# 12V_Power_Supply.net
KiCad netlist of a schematic drawn in Altium Designer
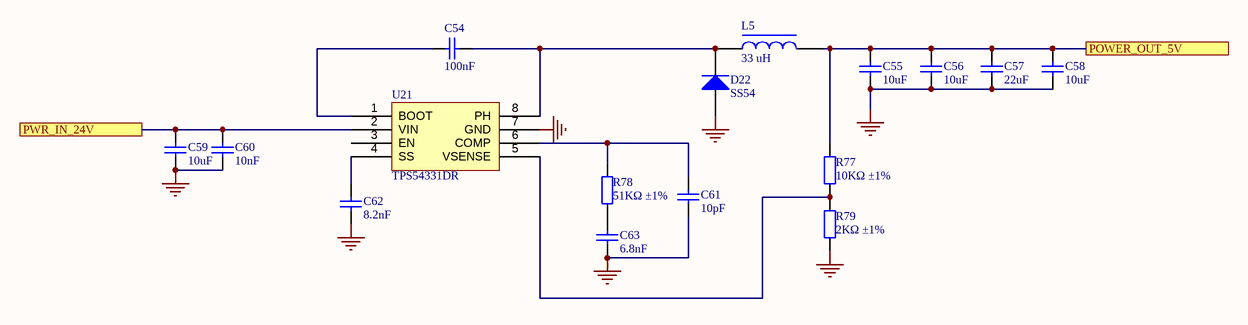
[diagram p0: 12V_Power_Supply.SchDoc]

(export (version "E")
  (design (tool "Eeschema 10.0.6"))
  (components
    (comp (ref "C54")
      (value "100nF")
      (footprint "0603_C")
      (description "Chip capacitors")
      (fields (field (name "MANUFACTURER") "YAGEO") (field (name "PARTNUMBER") "CC0603KRX7R9BB104"))
      (libsource (lib "Cap") (part "0603 100nF (104) 10% 50V"))
    )
    (comp (ref "C55")
      (value "10uF")
      (footprint "0603_C")
      (description "Chip capacitors")
      (fields
        (field (name "MANUFACTURER") "Samsung Electro-Mechanics")
        (field (name "PARTNUMBER") "CL10A106KP8NNNC")
      )
      (libsource (lib "Cap") (part "0603 10uF (106) 10% 10V"))
    )
    (comp (ref "C56")
      (value "10uF")
      (footprint "0603_C")
      (description "Chip capacitors")
      (fields
        (field (name "MANUFACTURER") "Samsung Electro-Mechanics")
        (field (name "PARTNUMBER") "CL10A106KP8NNNC")
      )
      (libsource (lib "Cap") (part "0603 10uF (106) 10% 10V"))
    )
    (comp (ref "C57")
      (value "22uF")
      (footprint "0805_C")
      (description "Chip capacitors")
      (fields
        (field (name "MANUFACTURER") "Samsung Electro-Mechanics")
        (field (name "PARTNUMBER") "CL21A226MAQNNNE")
      )
      (libsource (lib "Cap") (part "0805 22uF (226) 20% 25V"))
    )
    (comp (ref "C58")
      (value "10uF")
      (footprint "0603_C")
      (description "Chip capacitors")
      (fields
        (field (name "MANUFACTURER") "Samsung Electro-Mechanics")
        (field (name "PARTNUMBER") "CL10A106KP8NNNC")
      )
      (libsource (lib "Cap") (part "0603 10uF (106) 10% 10V"))
    )
    (comp (ref "C59")
      (value "10uF")
      (footprint "1206_C")
      (description "Chip capacitors")
      (fields
        (field (name "MANUFACTURER") "Samsung Electro-Mechanics")
        (field (name "PARTNUMBER") "CL31A106KBHNNNE")
      )
      (libsource (lib "Cap") (part "1206 10uF (106) 10% 50V"))
    )
    (comp (ref "C60")
      (value "10nF")
      (footprint "0402_C")
      (description "Chip capacitors")
      (fields
        (field (name "MANUFACTURER") "Samsung Electro-Mechanics")
        (field (name "PARTNUMBER") "CL05B103KB5NNNC")
      )
      (libsource (lib "Cap") (part "0402 10nF (103) 10% 50V"))
    )
    (comp (ref "C61")
      (value "10pF")
      (footprint "0402_C")
      (description "Chip capacitors")
      (fields
        (field (name "MANUFACTURER") "Samsung Electro-Mechanics")
        (field (name "PARTNUMBER") "CL05C100JB5NNNC")
      )
      (libsource (lib "Cap") (part "0402 10pF (100) 5% 50V"))
    )
    (comp (ref "C62")
      (value "8.2nF")
      (footprint "0603_C")
      (description "Chip capacitors")
      (fields
        (field (name "MANUFACTURER") "Samsung Electro-Mechanics")
        (field (name "PARTNUMBER") "CL10B822KB8NNNC")
      )
      (libsource (lib "Cap") (part "0603 8.2nF (822) 10% 50V"))
    )
    (comp (ref "C63")
      (value "6.8nF")
      (footprint "0402_C")
      (description "Chip capacitors")
      (fields
        (field (name "MANUFACTURER") "Guangdong Fenghua Advanced Tech")
        (field (name "PARTNUMBER") "0402B682K500NT")
      )
      (libsource (lib "Cap") (part "0402 6.8nF (682) 10% 50V"))
    )
    (comp (ref "D22")
      (value "SS54")
      (footprint "SMA(DO-214AC)_S1")
      (description "二极管")
      (libsource (lib "Diode") (part "SMA(DO-214AC) SS54"))
    )
    (comp (ref "L5")
      (value "33 uH")
      (footprint "INDPM7366X300N")
      (description "33uH ±20% 2A 270mΩ SMD,6.6x7.3x3.0mm Power Inductors RoHS")
      (libsource (lib "IUD") (part "1206 10uH 10%"))
    )
    (comp (ref "R77")
      (value "10KΩ ±1%")
      (footprint "0402_R")
      (description "Chip resistor")
      (fields (field (name "MANUFACTURER") "Uniroyal Elec") (field (name "PARTNUMBER") "0402WGF1002TCE"))
      (libsource (lib "RES") (part "0402 10K (1002) 1%"))
    )
    (comp (ref "R78")
      (value "51KΩ ±1%")
      (footprint "0402_R")
      (description "Chip resistor")
      (fields (field (name "MANUFACTURER") "Uniroyal Elec") (field (name "PARTNUMBER") "0402WGF5102TCE"))
      (libsource (lib "RES") (part "0402 51K (5102) 1%"))
    )
    (comp (ref "R79")
      (value "2KΩ ±1%")
      (footprint "0402_R")
      (description "Chip resistor")
      (fields (field (name "MANUFACTURER") "Uniroyal Elec") (field (name "PARTNUMBER") "0402WGF2001TCE"))
      (libsource (lib "RES") (part "0402 2K (2001) 1%"))
    )
    (comp (ref "U21")
      (value "TPS54331DR")
      (footprint "SOIC-8_150mil")
      (description "DC-DC芯片")
      (libsource (lib "IC") (part "TPS54331DR_[C9865]"))
    )
  )
  (nets
    (net (code "1") (name "/POWER_OUT_5V") (class "Default")
      (node (ref "C55") (pin "2") (pinfunction "2_2") (pintype "passive"))
      (node (ref "C56") (pin "2") (pinfunction "2_2") (pintype "passive"))
      (node (ref "C57") (pin "2") (pinfunction "2_2") (pintype "passive"))
      (node (ref "C58") (pin "2") (pinfunction "2_2") (pintype "passive"))
      (node (ref "L5") (pin "2") (pinfunction "2_2") (pintype "passive"))
      (node (ref "R77") (pin "2") (pinfunction "2_2") (pintype "passive"))
    )
    (net (code "2") (name "/PWR_IN_24V") (class "Default")
      (node (ref "C59") (pin "2") (pinfunction "2_2") (pintype "passive"))
      (node (ref "C60") (pin "2") (pinfunction "2_2") (pintype "passive"))
      (node (ref "U21") (pin "2") (pinfunction "VIN_2") (pintype "passive"))
    )
    (net (code "3") (name "GND") (class "Default")
      (node (ref "C55") (pin "1") (pinfunction "1_1") (pintype "passive"))
      (node (ref "C56") (pin "1") (pinfunction "1_1") (pintype "passive"))
      (node (ref "C57") (pin "1") (pinfunction "1_1") (pintype "passive"))
      (node (ref "C58") (pin "1") (pinfunction "1_1") (pintype "passive"))
      (node (ref "C59") (pin "1") (pinfunction "1_1") (pintype "passive"))
      (node (ref "C60") (pin "1") (pinfunction "1_1") (pintype "passive"))
      (node (ref "C61") (pin "1") (pinfunction "1_1") (pintype "passive"))
      (node (ref "C62") (pin "1") (pinfunction "1_1") (pintype "passive"))
      (node (ref "C63") (pin "1") (pinfunction "1_1") (pintype "passive"))
      (node (ref "D22") (pin "1") (pinfunction "A_1") (pintype "passive"))
      (node (ref "R79") (pin "1") (pinfunction "1_1") (pintype "passive"))
      (node (ref "U21") (pin "7") (pinfunction "GND_7") (pintype "passive"))
    )
    (net (code "4") (name "Net-(C63-Pad2)") (class "Default")
      (node (ref "C63") (pin "2") (pinfunction "2_2") (pintype "passive"))
      (node (ref "R78") (pin "1") (pinfunction "1_1") (pintype "passive"))
    )
    (net (code "5") (name "Net-(D22-K)") (class "Default")
      (node (ref "C54") (pin "2") (pinfunction "2_2") (pintype "passive"))
      (node (ref "D22") (pin "2") (pinfunction "K_2") (pintype "passive"))
      (node (ref "L5") (pin "1") (pinfunction "1_1") (pintype "passive"))
      (node (ref "U21") (pin "8") (pinfunction "PH_8") (pintype "passive"))
    )
    (net (code "6") (name "Net-(U21-BOOT)") (class "Default")
      (node (ref "C54") (pin "1") (pinfunction "1_1") (pintype "passive"))
      (node (ref "U21") (pin "1") (pinfunction "BOOT_1") (pintype "passive"))
    )
    (net (code "7") (name "Net-(U21-COMP)") (class "Default")
      (node (ref "C61") (pin "2") (pinfunction "2_2") (pintype "passive"))
      (node (ref "R78") (pin "2") (pinfunction "2_2") (pintype "passive"))
      (node (ref "U21") (pin "6") (pinfunction "COMP_6") (pintype "passive"))
    )
    (net (code "8") (name "Net-(U21-SS)") (class "Default")
      (node (ref "C62") (pin "2") (pinfunction "2_2") (pintype "passive"))
      (node (ref "U21") (pin "4") (pinfunction "SS_4") (pintype "passive"))
    )
    (net (code "9") (name "Net-(U21-VSENSE)") (class "Default")
      (node (ref "R77") (pin "1") (pinfunction "1_1") (pintype "passive"))
      (node (ref "R79") (pin "2") (pinfunction "2_2") (pintype "passive"))
      (node (ref "U21") (pin "5") (pinfunction "VSENSE_5") (pintype "passive"))
    )
    (net (code "10") (name "unconnected-(U21-EN-Pad3)") (class "Default")
      (node (ref "U21") (pin "3") (pinfunction "EN_3") (pintype "passive"))
    )
  )
)
